# EMMC_CHIP.net
KiCad netlist of a schematic drawn in Altium Designer
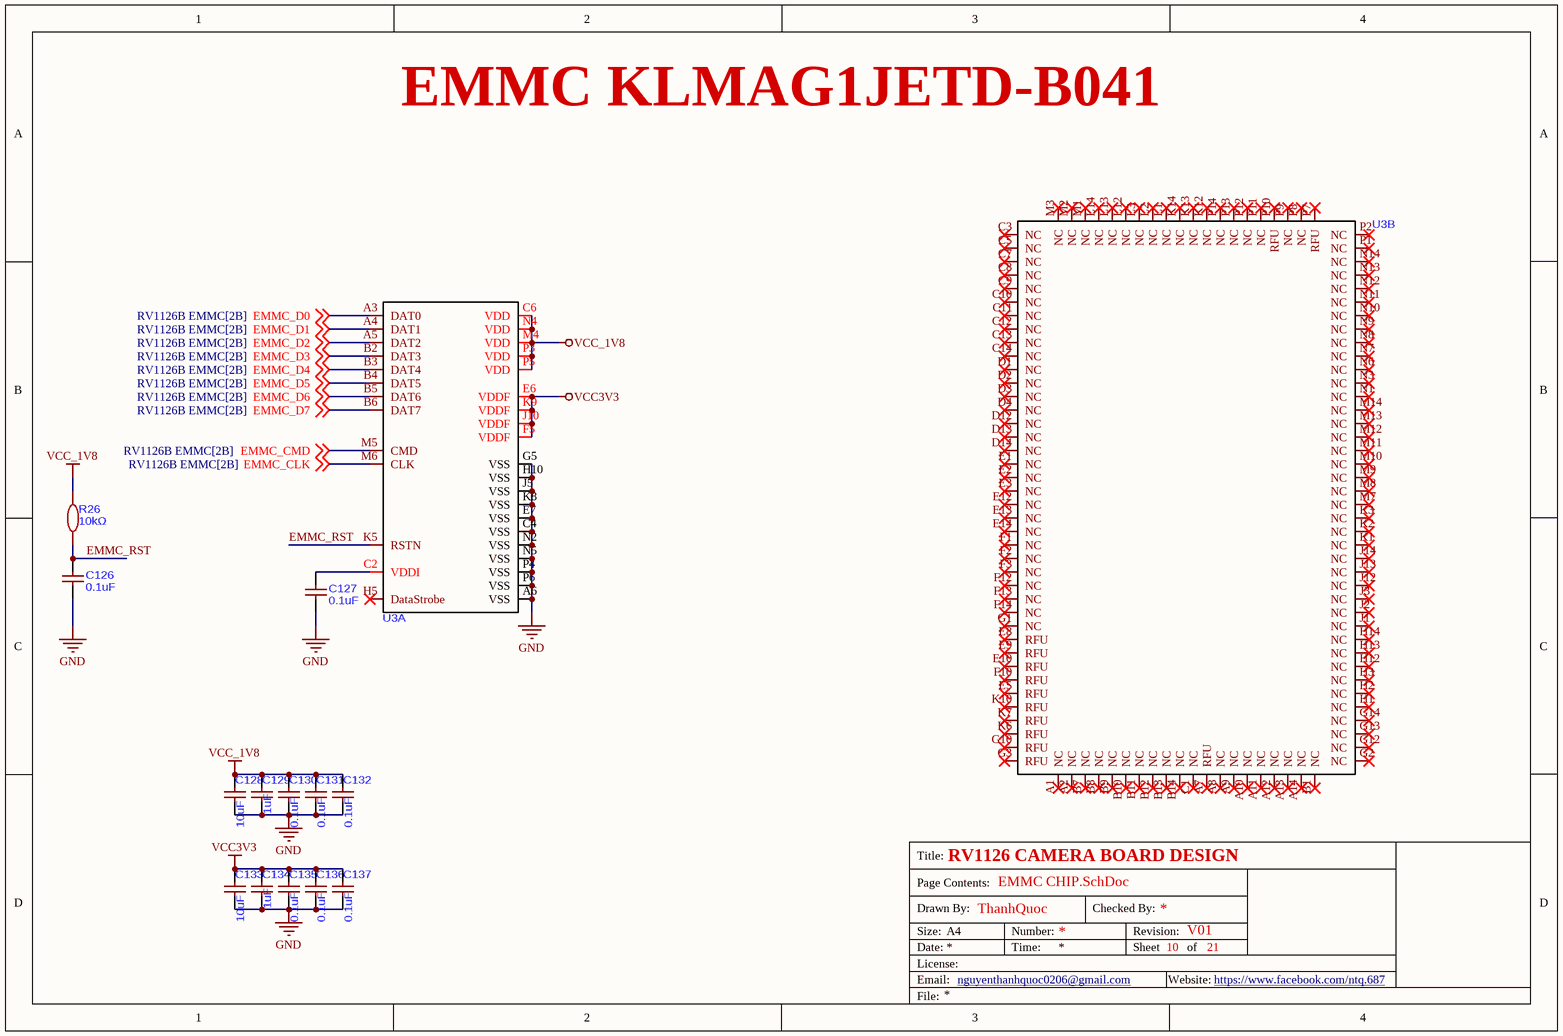
[diagram p0: EMMC CHIP.SchDoc]

(export (version "E")
  (design (tool "Eeschema 10.0.6"))
  (components
    (comp (ref "C126")
      (value "0.1uF")
      (footprint "C0201")
      (description "0.1uF ±10% 6.3V Ceramic Capacitor X5R 0201")
      (libsource (lib "Schlib1") (part "CAP_100nF-6.3V-10%-0201_1"))
    )
    (comp (ref "C127")
      (value "0.1uF")
      (footprint "C0201")
      (description "0.1uF ±10% 6.3V Ceramic Capacitor X5R 0201")
      (libsource (lib "Schlib1") (part "CAP_100nF-6.3V-10%-0201_1"))
    )
    (comp (ref "C128")
      (value "10uF")
      (footprint "C0402")
      (description "10µF ±20% 10V Ceramic Capacitor X5R 0402 (1005 Metric)")
      (libsource (lib "Schlib1") (part "CAP_10uF-10V-20%-0402"))
    )
    (comp (ref "C129")
      (value "1uF")
      (footprint "C0201")
      (description "1uF ±10% 6.3V Ceramic Capacitor X5R 0201")
      (libsource (lib "Schlib1") (part "CAP_1uF-6.3V-10%-0201"))
    )
    (comp (ref "C130")
      (value "0.1uF")
      (footprint "C0201")
      (description "0.1uF ±10% 6.3V Ceramic Capacitor X5R 0201")
      (libsource (lib "Schlib1") (part "CAP_100nF-6.3V-10%-0201_1"))
    )
    (comp (ref "C131")
      (value "0.1uF")
      (footprint "C0201")
      (description "0.1uF ±10% 6.3V Ceramic Capacitor X5R 0201")
      (libsource (lib "Schlib1") (part "CAP_100nF-6.3V-10%-0201_1"))
    )
    (comp (ref "C132")
      (value "0.1uF")
      (footprint "C0201")
      (description "0.1uF ±10% 6.3V Ceramic Capacitor X5R 0201")
      (libsource (lib "Schlib1") (part "CAP_100nF-6.3V-10%-0201_1"))
    )
    (comp (ref "C133")
      (value "10uF")
      (footprint "C0402")
      (description "10µF ±20% 10V Ceramic Capacitor X5R 0402 (1005 Metric)")
      (libsource (lib "Schlib1") (part "CAP_10uF-10V-20%-0402"))
    )
    (comp (ref "C134")
      (value "1uF")
      (footprint "C0201")
      (description "1uF ±10% 6.3V Ceramic Capacitor X5R 0201")
      (libsource (lib "Schlib1") (part "CAP_1uF-6.3V-10%-0201"))
    )
    (comp (ref "C135")
      (value "0.1uF")
      (footprint "C0201")
      (description "0.1uF ±10% 6.3V Ceramic Capacitor X5R 0201")
      (libsource (lib "Schlib1") (part "CAP_100nF-6.3V-10%-0201_1"))
    )
    (comp (ref "C136")
      (value "0.1uF")
      (footprint "C0201")
      (description "0.1uF ±10% 6.3V Ceramic Capacitor X5R 0201")
      (libsource (lib "Schlib1") (part "CAP_100nF-6.3V-10%-0201_1"))
    )
    (comp (ref "C137")
      (value "0.1uF")
      (footprint "C0201")
      (description "0.1uF ±10% 6.3V Ceramic Capacitor X5R 0201")
      (libsource (lib "Schlib1") (part "CAP_100nF-6.3V-10%-0201_1"))
    )
    (comp (ref "R26")
      (value "10kΩ")
      (footprint "R0201")
      (description "RES 10KΩ ±1% 50mW 0201")
      (libsource (lib "Schlib1") (part "RES_10K-50mW-1%-0201"))
    )
    (comp (ref "U3")
      (value "emmc 16gb")
      (footprint "FBGA-153_L13.0-W11.5-P0.50_KLMAG1JETD-B041")
      (description "eMMC 5.1 Specification compatibility")
      (libsource (lib "Schlib1") (part "KLMAG1JETD-B041"))
    )
  )
  (nets
    (net (code "1") (name "/EMMC_RST") (class "Default")
      (node (ref "C126") (pin "2") (pinfunction "2_2") (pintype "passive"))
      (node (ref "R26") (pin "1") (pinfunction "1_1") (pintype "passive"))
      (node (ref "U3") (pin "K5") (pinfunction "RSTN_K5") (pintype "passive"))
    )
    (net (code "2") (name "EMMC_CLK") (class "Default")
      (node (ref "U3") (pin "M6") (pinfunction "CLK_M6") (pintype "passive"))
    )
    (net (code "3") (name "EMMC_CMD") (class "Default")
      (node (ref "U3") (pin "M5") (pinfunction "CMD_M5") (pintype "passive"))
    )
    (net (code "4") (name "EMMC_D0") (class "Default")
      (node (ref "U3") (pin "A3") (pinfunction "DAT0_A3") (pintype "passive"))
    )
    (net (code "5") (name "EMMC_D1") (class "Default")
      (node (ref "U3") (pin "A4") (pinfunction "DAT1_A4") (pintype "passive"))
    )
    (net (code "6") (name "EMMC_D2") (class "Default")
      (node (ref "U3") (pin "A5") (pinfunction "DAT2_A5") (pintype "passive"))
    )
    (net (code "7") (name "EMMC_D3") (class "Default")
      (node (ref "U3") (pin "B2") (pinfunction "DAT3_B2") (pintype "passive"))
    )
    (net (code "8") (name "EMMC_D4") (class "Default")
      (node (ref "U3") (pin "B3") (pinfunction "DAT4_B3") (pintype "passive"))
    )
    (net (code "9") (name "EMMC_D5") (class "Default")
      (node (ref "U3") (pin "B4") (pinfunction "DAT5_B4") (pintype "passive"))
    )
    (net (code "10") (name "EMMC_D6") (class "Default")
      (node (ref "U3") (pin "B5") (pinfunction "DAT6_B5") (pintype "passive"))
    )
    (net (code "11") (name "EMMC_D7") (class "Default")
      (node (ref "U3") (pin "B6") (pinfunction "DAT7_B6") (pintype "passive"))
    )
    (net (code "12") (name "GND") (class "Default")
      (node (ref "C126") (pin "1") (pinfunction "1_1") (pintype "passive"))
      (node (ref "C127") (pin "1") (pinfunction "1_1") (pintype "passive"))
      (node (ref "C128") (pin "1") (pinfunction "1_1") (pintype "passive"))
      (node (ref "C129") (pin "1") (pinfunction "1_1") (pintype "passive"))
      (node (ref "C130") (pin "1") (pinfunction "1_1") (pintype "passive"))
      (node (ref "C131") (pin "1") (pinfunction "1_1") (pintype "passive"))
      (node (ref "C132") (pin "1") (pinfunction "1_1") (pintype "passive"))
      (node (ref "C133") (pin "1") (pinfunction "1_1") (pintype "passive"))
      (node (ref "C134") (pin "1") (pinfunction "1_1") (pintype "passive"))
      (node (ref "C135") (pin "1") (pinfunction "1_1") (pintype "passive"))
      (node (ref "C136") (pin "1") (pinfunction "1_1") (pintype "passive"))
      (node (ref "C137") (pin "1") (pinfunction "1_1") (pintype "passive"))
      (node (ref "U3") (pin "A6") (pinfunction "VSS_A6") (pintype "passive"))
      (node (ref "U3") (pin "C4") (pinfunction "VSS_C4") (pintype "passive"))
      (node (ref "U3") (pin "E7") (pinfunction "VSS_E7") (pintype "passive"))
      (node (ref "U3") (pin "G5") (pinfunction "VSS_G5") (pintype "passive"))
      (node (ref "U3") (pin "H10") (pinfunction "VSS_H10") (pintype "passive"))
      (node (ref "U3") (pin "J5") (pinfunction "VSS_J5") (pintype "passive"))
      (node (ref "U3") (pin "K8") (pinfunction "VSS_K8") (pintype "passive"))
      (node (ref "U3") (pin "N2") (pinfunction "VSS_N2") (pintype "passive"))
      (node (ref "U3") (pin "N5") (pinfunction "VSS_N5") (pintype "passive"))
      (node (ref "U3") (pin "P4") (pinfunction "VSS_P4") (pintype "passive"))
      (node (ref "U3") (pin "P6") (pinfunction "VSS_P6") (pintype "passive"))
    )
    (net (code "13") (name "Net-(U3A-VDDI)") (class "Default")
      (node (ref "C127") (pin "2") (pinfunction "2_2") (pintype "passive"))
      (node (ref "U3") (pin "C2") (pinfunction "VDDI_C2") (pintype "passive"))
    )
    (net (code "14") (name "VCC3V3") (class "Default")
      (node (ref "C133") (pin "2") (pinfunction "2_2") (pintype "passive"))
      (node (ref "C134") (pin "2") (pinfunction "2_2") (pintype "passive"))
      (node (ref "C135") (pin "2") (pinfunction "2_2") (pintype "passive"))
      (node (ref "C136") (pin "2") (pinfunction "2_2") (pintype "passive"))
      (node (ref "C137") (pin "2") (pinfunction "2_2") (pintype "passive"))
      (node (ref "U3") (pin "E6") (pinfunction "VDDF_E6") (pintype "passive"))
      (node (ref "U3") (pin "F5") (pinfunction "VDDF_F5") (pintype "passive"))
      (node (ref "U3") (pin "J10") (pinfunction "VDDF_J10") (pintype "passive"))
      (node (ref "U3") (pin "K9") (pinfunction "VDDF_K9") (pintype "passive"))
    )
    (net (code "15") (name "VCC_1V8") (class "Default")
      (node (ref "C128") (pin "2") (pinfunction "2_2") (pintype "passive"))
      (node (ref "C129") (pin "2") (pinfunction "2_2") (pintype "passive"))
      (node (ref "C130") (pin "2") (pinfunction "2_2") (pintype "passive"))
      (node (ref "C131") (pin "2") (pinfunction "2_2") (pintype "passive"))
      (node (ref "C132") (pin "2") (pinfunction "2_2") (pintype "passive"))
      (node (ref "R26") (pin "2") (pinfunction "2_2") (pintype "passive"))
      (node (ref "U3") (pin "C6") (pinfunction "VDD_C6") (pintype "passive"))
      (node (ref "U3") (pin "M4") (pinfunction "VDD_M4") (pintype "passive"))
      (node (ref "U3") (pin "N4") (pinfunction "VDD_N4") (pintype "passive"))
      (node (ref "U3") (pin "P3") (pinfunction "VDD_P3") (pintype "passive"))
      (node (ref "U3") (pin "P5") (pinfunction "VDD_P5") (pintype "passive"))
    )
    (net (code "16") (name "unconnected-(U3A-DataStrobe-PadH5)") (class "Default")
      (node (ref "U3") (pin "H5") (pinfunction "DataStrobe_H5") (pintype "passive+no_connect"))
    )
    (net (code "17") (name "unconnected-(U3B-NC-PadA1)") (class "Default")
      (node (ref "U3") (pin "A1") (pinfunction "NC_A1") (pintype "passive+no_connect"))
    )
    (net (code "18") (name "unconnected-(U3B-NC-PadA2)") (class "Default")
      (node (ref "U3") (pin "A2") (pinfunction "NC_A2") (pintype "passive+no_connect"))
    )
    (net (code "19") (name "unconnected-(U3B-NC-PadA8)") (class "Default")
      (node (ref "U3") (pin "A8") (pinfunction "NC_A8") (pintype "passive+no_connect"))
    )
    (net (code "20") (name "unconnected-(U3B-NC-PadA9)") (class "Default")
      (node (ref "U3") (pin "A9") (pinfunction "NC_A9") (pintype "passive+no_connect"))
    )
    (net (code "21") (name "unconnected-(U3B-NC-PadA10)") (class "Default")
      (node (ref "U3") (pin "A10") (pinfunction "NC_A10") (pintype "passive+no_connect"))
    )
    (net (code "22") (name "unconnected-(U3B-NC-PadA11)") (class "Default")
      (node (ref "U3") (pin "A11") (pinfunction "NC_A11") (pintype "passive+no_connect"))
    )
    (net (code "23") (name "unconnected-(U3B-NC-PadA12)") (class "Default")
      (node (ref "U3") (pin "A12") (pinfunction "NC_A12") (pintype "passive+no_connect"))
    )
    (net (code "24") (name "unconnected-(U3B-NC-PadA13)") (class "Default")
      (node (ref "U3") (pin "A13") (pinfunction "NC_A13") (pintype "passive+no_connect"))
    )
    (net (code "25") (name "unconnected-(U3B-NC-PadA14)") (class "Default")
      (node (ref "U3") (pin "A14") (pinfunction "NC_A14") (pintype "passive+no_connect"))
    )
    (net (code "26") (name "unconnected-(U3B-NC-PadB1)") (class "Default")
      (node (ref "U3") (pin "B1") (pinfunction "NC_B1") (pintype "passive+no_connect"))
    )
    (net (code "27") (name "unconnected-(U3B-NC-PadB7)") (class "Default")
      (node (ref "U3") (pin "B7") (pinfunction "NC_B7") (pintype "passive+no_connect"))
    )
    (net (code "28") (name "unconnected-(U3B-NC-PadB8)") (class "Default")
      (node (ref "U3") (pin "B8") (pinfunction "NC_B8") (pintype "passive+no_connect"))
    )
    (net (code "29") (name "unconnected-(U3B-NC-PadB9)") (class "Default")
      (node (ref "U3") (pin "B9") (pinfunction "NC_B9") (pintype "passive+no_connect"))
    )
    (net (code "30") (name "unconnected-(U3B-NC-PadB10)") (class "Default")
      (node (ref "U3") (pin "B10") (pinfunction "NC_B10") (pintype "passive+no_connect"))
    )
    (net (code "31") (name "unconnected-(U3B-NC-PadB11)") (class "Default")
      (node (ref "U3") (pin "B11") (pinfunction "NC_B11") (pintype "passive+no_connect"))
    )
    (net (code "32") (name "unconnected-(U3B-NC-PadB12)") (class "Default")
      (node (ref "U3") (pin "B12") (pinfunction "NC_B12") (pintype "passive+no_connect"))
    )
    (net (code "33") (name "unconnected-(U3B-NC-PadB13)") (class "Default")
      (node (ref "U3") (pin "B13") (pinfunction "NC_B13") (pintype "passive+no_connect"))
    )
    (net (code "34") (name "unconnected-(U3B-NC-PadB14)") (class "Default")
      (node (ref "U3") (pin "B14") (pinfunction "NC_B14") (pintype "passive+no_connect"))
    )
    (net (code "35") (name "unconnected-(U3B-NC-PadC1)") (class "Default")
      (node (ref "U3") (pin "C1") (pinfunction "NC_C1") (pintype "passive+no_connect"))
    )
    (net (code "36") (name "unconnected-(U3B-NC-PadC3)") (class "Default")
      (node (ref "U3") (pin "C3") (pinfunction "NC_C3") (pintype "passive+no_connect"))
    )
    (net (code "37") (name "unconnected-(U3B-NC-PadC5)") (class "Default")
      (node (ref "U3") (pin "C5") (pinfunction "NC_C5") (pintype "passive+no_connect"))
    )
    (net (code "38") (name "unconnected-(U3B-NC-PadC7)") (class "Default")
      (node (ref "U3") (pin "C7") (pinfunction "NC_C7") (pintype "passive+no_connect"))
    )
    (net (code "39") (name "unconnected-(U3B-NC-PadC8)") (class "Default")
      (node (ref "U3") (pin "C8") (pinfunction "NC_C8") (pintype "passive+no_connect"))
    )
    (net (code "40") (name "unconnected-(U3B-NC-PadC9)") (class "Default")
      (node (ref "U3") (pin "C9") (pinfunction "NC_C9") (pintype "passive+no_connect"))
    )
    (net (code "41") (name "unconnected-(U3B-NC-PadC10)") (class "Default")
      (node (ref "U3") (pin "C10") (pinfunction "NC_C10") (pintype "passive+no_connect"))
    )
    (net (code "42") (name "unconnected-(U3B-NC-PadC11)") (class "Default")
      (node (ref "U3") (pin "C11") (pinfunction "NC_C11") (pintype "passive+no_connect"))
    )
    (net (code "43") (name "unconnected-(U3B-NC-PadC12)") (class "Default")
      (node (ref "U3") (pin "C12") (pinfunction "NC_C12") (pintype "passive+no_connect"))
    )
    (net (code "44") (name "unconnected-(U3B-NC-PadC13)") (class "Default")
      (node (ref "U3") (pin "C13") (pinfunction "NC_C13") (pintype "passive+no_connect"))
    )
    (net (code "45") (name "unconnected-(U3B-NC-PadC14)") (class "Default")
      (node (ref "U3") (pin "C14") (pinfunction "NC_C14") (pintype "passive+no_connect"))
    )
    (net (code "46") (name "unconnected-(U3B-NC-PadD1)") (class "Default")
      (node (ref "U3") (pin "D1") (pinfunction "NC_D1") (pintype "passive+no_connect"))
    )
    (net (code "47") (name "unconnected-(U3B-NC-PadD2)") (class "Default")
      (node (ref "U3") (pin "D2") (pinfunction "NC_D2") (pintype "passive+no_connect"))
    )
    (net (code "48") (name "unconnected-(U3B-NC-PadD3)") (class "Default")
      (node (ref "U3") (pin "D3") (pinfunction "NC_D3") (pintype "passive+no_connect"))
    )
    (net (code "49") (name "unconnected-(U3B-NC-PadD4)") (class "Default")
      (node (ref "U3") (pin "D4") (pinfunction "NC_D4") (pintype "passive+no_connect"))
    )
    (net (code "50") (name "unconnected-(U3B-NC-PadD12)") (class "Default")
      (node (ref "U3") (pin "D12") (pinfunction "NC_D12") (pintype "passive+no_connect"))
    )
    (net (code "51") (name "unconnected-(U3B-NC-PadD13)") (class "Default")
      (node (ref "U3") (pin "D13") (pinfunction "NC_D13") (pintype "passive+no_connect"))
    )
    (net (code "52") (name "unconnected-(U3B-NC-PadD14)") (class "Default")
      (node (ref "U3") (pin "D14") (pinfunction "NC_D14") (pintype "passive+no_connect"))
    )
    (net (code "53") (name "unconnected-(U3B-NC-PadE1)") (class "Default")
      (node (ref "U3") (pin "E1") (pinfunction "NC_E1") (pintype "passive+no_connect"))
    )
    (net (code "54") (name "unconnected-(U3B-NC-PadE2)") (class "Default")
      (node (ref "U3") (pin "E2") (pinfunction "NC_E2") (pintype "passive+no_connect"))
    )
    (net (code "55") (name "unconnected-(U3B-NC-PadE3)") (class "Default")
      (node (ref "U3") (pin "E3") (pinfunction "NC_E3") (pintype "passive+no_connect"))
    )
    (net (code "56") (name "unconnected-(U3B-NC-PadE12)") (class "Default")
      (node (ref "U3") (pin "E12") (pinfunction "NC_E12") (pintype "passive+no_connect"))
    )
    (net (code "57") (name "unconnected-(U3B-NC-PadE13)") (class "Default")
      (node (ref "U3") (pin "E13") (pinfunction "NC_E13") (pintype "passive+no_connect"))
    )
    (net (code "58") (name "unconnected-(U3B-NC-PadE14)") (class "Default")
      (node (ref "U3") (pin "E14") (pinfunction "NC_E14") (pintype "passive+no_connect"))
    )
    (net (code "59") (name "unconnected-(U3B-NC-PadF1)") (class "Default")
      (node (ref "U3") (pin "F1") (pinfunction "NC_F1") (pintype "passive+no_connect"))
    )
    (net (code "60") (name "unconnected-(U3B-NC-PadF2)") (class "Default")
      (node (ref "U3") (pin "F2") (pinfunction "NC_F2") (pintype "passive+no_connect"))
    )
    (net (code "61") (name "unconnected-(U3B-NC-PadF3)") (class "Default")
      (node (ref "U3") (pin "F3") (pinfunction "NC_F3") (pintype "passive+no_connect"))
    )
    (net (code "62") (name "unconnected-(U3B-NC-PadF12)") (class "Default")
      (node (ref "U3") (pin "F12") (pinfunction "NC_F12") (pintype "passive+no_connect"))
    )
    (net (code "63") (name "unconnected-(U3B-NC-PadF13)") (class "Default")
      (node (ref "U3") (pin "F13") (pinfunction "NC_F13") (pintype "passive+no_connect"))
    )
    (net (code "64") (name "unconnected-(U3B-NC-PadF14)") (class "Default")
      (node (ref "U3") (pin "F14") (pinfunction "NC_F14") (pintype "passive+no_connect"))
    )
    (net (code "65") (name "unconnected-(U3B-NC-PadG1)") (class "Default")
      (node (ref "U3") (pin "G1") (pinfunction "NC_G1") (pintype "passive+no_connect"))
    )
    (net (code "66") (name "unconnected-(U3B-NC-PadG2)") (class "Default")
      (node (ref "U3") (pin "G2") (pinfunction "NC_G2") (pintype "passive+no_connect"))
    )
    (net (code "67") (name "unconnected-(U3B-NC-PadG12)") (class "Default")
      (node (ref "U3") (pin "G12") (pinfunction "NC_G12") (pintype "passive+no_connect"))
    )
    (net (code "68") (name "unconnected-(U3B-NC-PadG13)") (class "Default")
      (node (ref "U3") (pin "G13") (pinfunction "NC_G13") (pintype "passive+no_connect"))
    )
    (net (code "69") (name "unconnected-(U3B-NC-PadG14)") (class "Default")
      (node (ref "U3") (pin "G14") (pinfunction "NC_G14") (pintype "passive+no_connect"))
    )
    (net (code "70") (name "unconnected-(U3B-NC-PadH1)") (class "Default")
      (node (ref "U3") (pin "H1") (pinfunction "NC_H1") (pintype "passive+no_connect"))
    )
    (net (code "71") (name "unconnected-(U3B-NC-PadH2)") (class "Default")
      (node (ref "U3") (pin "H2") (pinfunction "NC_H2") (pintype "passive+no_connect"))
    )
    (net (code "72") (name "unconnected-(U3B-NC-PadH3)") (class "Default")
      (node (ref "U3") (pin "H3") (pinfunction "NC_H3") (pintype "passive+no_connect"))
    )
    (net (code "73") (name "unconnected-(U3B-NC-PadH12)") (class "Default")
      (node (ref "U3") (pin "H12") (pinfunction "NC_H12") (pintype "passive+no_connect"))
    )
    (net (code "74") (name "unconnected-(U3B-NC-PadH13)") (class "Default")
      (node (ref "U3") (pin "H13") (pinfunction "NC_H13") (pintype "passive+no_connect"))
    )
    (net (code "75") (name "unconnected-(U3B-NC-PadH14)") (class "Default")
      (node (ref "U3") (pin "H14") (pinfunction "NC_H14") (pintype "passive+no_connect"))
    )
    (net (code "76") (name "unconnected-(U3B-NC-PadJ1)") (class "Default")
      (node (ref "U3") (pin "J1") (pinfunction "NC_J1") (pintype "passive+no_connect"))
    )
    (net (code "77") (name "unconnected-(U3B-NC-PadJ2)") (class "Default")
      (node (ref "U3") (pin "J2") (pinfunction "NC_J2") (pintype "passive+no_connect"))
    )
    (net (code "78") (name "unconnected-(U3B-NC-PadJ3)") (class "Default")
      (node (ref "U3") (pin "J3") (pinfunction "NC_J3") (pintype "passive+no_connect"))
    )
    (net (code "79") (name "unconnected-(U3B-NC-PadJ12)") (class "Default")
      (node (ref "U3") (pin "J12") (pinfunction "NC_J12") (pintype "passive+no_connect"))
    )
    (net (code "80") (name "unconnected-(U3B-NC-PadJ13)") (class "Default")
      (node (ref "U3") (pin "J13") (pinfunction "NC_J13") (pintype "passive+no_connect"))
    )
    (net (code "81") (name "unconnected-(U3B-NC-PadJ14)") (class "Default")
      (node (ref "U3") (pin "J14") (pinfunction "NC_J14") (pintype "passive+no_connect"))
    )
    (net (code "82") (name "unconnected-(U3B-NC-PadK1)") (class "Default")
      (node (ref "U3") (pin "K1") (pinfunction "NC_K1") (pintype "passive+no_connect"))
    )
    (net (code "83") (name "unconnected-(U3B-NC-PadK2)") (class "Default")
      (node (ref "U3") (pin "K2") (pinfunction "NC_K2") (pintype "passive+no_connect"))
    )
    (net (code "84") (name "unconnected-(U3B-NC-PadK3)") (class "Default")
      (node (ref "U3") (pin "K3") (pinfunction "NC_K3") (pintype "passive+no_connect"))
    )
    (net (code "85") (name "unconnected-(U3B-NC-PadK12)") (class "Default")
      (node (ref "U3") (pin "K12") (pinfunction "NC_K12") (pintype "passive+no_connect"))
    )
    (net (code "86") (name "unconnected-(U3B-NC-PadK13)") (class "Default")
      (node (ref "U3") (pin "K13") (pinfunction "NC_K13") (pintype "passive+no_connect"))
    )
    (net (code "87") (name "unconnected-(U3B-NC-PadK14)") (class "Default")
      (node (ref "U3") (pin "K14") (pinfunction "NC_K14") (pintype "passive+no_connect"))
    )
    (net (code "88") (name "unconnected-(U3B-NC-PadL1)") (class "Default")
      (node (ref "U3") (pin "L1") (pinfunction "NC_L1") (pintype "passive+no_connect"))
    )
    (net (code "89") (name "unconnected-(U3B-NC-PadL2)") (class "Default")
      (node (ref "U3") (pin "L2") (pinfunction "NC_L2") (pintype "passive+no_connect"))
    )
    (net (code "90") (name "unconnected-(U3B-NC-PadL3)") (class "Default")
      (node (ref "U3") (pin "L3") (pinfunction "NC_L3") (pintype "passive+no_connect"))
    )
    (net (code "91") (name "unconnected-(U3B-NC-PadL12)") (class "Default")
      (node (ref "U3") (pin "L12") (pinfunction "NC_L12") (pintype "passive+no_connect"))
    )
    (net (code "92") (name "unconnected-(U3B-NC-PadL13)") (class "Default")
      (node (ref "U3") (pin "L13") (pinfunction "NC_L13") (pintype "passive+no_connect"))
    )
    (net (code "93") (name "unconnected-(U3B-NC-PadL14)") (class "Default")
      (node (ref "U3") (pin "L14") (pinfunction "NC_L14") (pintype "passive+no_connect"))
    )
    (net (code "94") (name "unconnected-(U3B-NC-PadM1)") (class "Default")
      (node (ref "U3") (pin "M1") (pinfunction "NC_M1") (pintype "passive+no_connect"))
    )
    (net (code "95") (name "unconnected-(U3B-NC-PadM2)") (class "Default")
      (node (ref "U3") (pin "M2") (pinfunction "NC_M2") (pintype "passive+no_connect"))
    )
    (net (code "96") (name "unconnected-(U3B-NC-PadM3)") (class "Default")
      (node (ref "U3") (pin "M3") (pinfunction "NC_M3") (pintype "passive+no_connect"))
    )
    (net (code "97") (name "unconnected-(U3B-NC-PadM7)") (class "Default")
      (node (ref "U3") (pin "M7") (pinfunction "NC_M7") (pintype "passive+no_connect"))
    )
    (net (code "98") (name "unconnected-(U3B-NC-PadM8)") (class "Default")
      (node (ref "U3") (pin "M8") (pinfunction "NC_M8") (pintype "passive+no_connect"))
    )
    (net (code "99") (name "unconnected-(U3B-NC-PadM9)") (class "Default")
      (node (ref "U3") (pin "M9") (pinfunction "NC_M9") (pintype "passive+no_connect"))
    )
    (net (code "100") (name "unconnected-(U3B-NC-PadM10)") (class "Default")
      (node (ref "U3") (pin "M10") (pinfunction "NC_M10") (pintype "passive+no_connect"))
    )
    (net (code "101") (name "unconnected-(U3B-NC-PadM11)") (class "Default")
      (node (ref "U3") (pin "M11") (pinfunction "NC_M11") (pintype "passive+no_connect"))
    )
    (net (code "102") (name "unconnected-(U3B-NC-PadM12)") (class "Default")
      (node (ref "U3") (pin "M12") (pinfunction "NC_M12") (pintype "passive+no_connect"))
    )
    (net (code "103") (name "unconnected-(U3B-NC-PadM13)") (class "Default")
      (node (ref "U3") (pin "M13") (pinfunction "NC_M13") (pintype "passive+no_connect"))
    )
    (net (code "104") (name "unconnected-(U3B-NC-PadM14)") (class "Default")
      (node (ref "U3") (pin "M14") (pinfunction "NC_M14") (pintype "passive+no_connect"))
    )
    (net (code "105") (name "unconnected-(U3B-NC-PadN1)") (class "Default")
      (node (ref "U3") (pin "N1") (pinfunction "NC_N1") (pintype "passive+no_connect"))
    )
    (net (code "106") (name "unconnected-(U3B-NC-PadN3)") (class "Default")
      (node (ref "U3") (pin "N3") (pinfunction "NC_N3") (pintype "passive+no_connect"))
    )
    (net (code "107") (name "unconnected-(U3B-NC-PadN6)") (class "Default")
      (node (ref "U3") (pin "N6") (pinfunction "NC_N6") (pintype "passive+no_connect"))
    )
    (net (code "108") (name "unconnected-(U3B-NC-PadN7)") (class "Default")
      (node (ref "U3") (pin "N7") (pinfunction "NC_N7") (pintype "passive+no_connect"))
    )
    (net (code "109") (name "unconnected-(U3B-NC-PadN8)") (class "Default")
      (node (ref "U3") (pin "N8") (pinfunction "NC_N8") (pintype "passive+no_connect"))
    )
    (net (code "110") (name "unconnected-(U3B-NC-PadN9)") (class "Default")
      (node (ref "U3") (pin "N9") (pinfunction "NC_N9") (pintype "passive+no_connect"))
    )
    (net (code "111") (name "unconnected-(U3B-NC-PadN10)") (class "Default")
      (node (ref "U3") (pin "N10") (pinfunction "NC_N10") (pintype "passive+no_connect"))
    )
    (net (code "112") (name "unconnected-(U3B-NC-PadN11)") (class "Default")
      (node (ref "U3") (pin "N11") (pinfunction "NC_N11") (pintype "passive+no_connect"))
    )
    (net (code "113") (name "unconnected-(U3B-NC-PadN12)") (class "Default")
      (node (ref "U3") (pin "N12") (pinfunction "NC_N12") (pintype "passive+no_connect"))
    )
    (net (code "114") (name "unconnected-(U3B-NC-PadN13)") (class "Default")
      (node (ref "U3") (pin "N13") (pinfunction "NC_N13") (pintype "passive+no_connect"))
    )
    (net (code "115") (name "unconnected-(U3B-NC-PadN14)") (class "Default")
      (node (ref "U3") (pin "N14") (pinfunction "NC_N14") (pintype "passive+no_connect"))
    )
    (net (code "116") (name "unconnected-(U3B-NC-PadP1)") (class "Default")
      (node (ref "U3") (pin "P1") (pinfunction "NC_P1") (pintype "passive+no_connect"))
    )
    (net (code "117") (name "unconnected-(U3B-NC-PadP2)") (class "Default")
      (node (ref "U3") (pin "P2") (pinfunction "NC_P2") (pintype "passive+no_connect"))
    )
    (net (code "118") (name "unconnected-(U3B-NC-PadP8)") (class "Default")
      (node (ref "U3") (pin "P8") (pinfunction "NC_P8") (pintype "passive+no_connect"))
    )
    (net (code "119") (name "unconnected-(U3B-NC-PadP9)") (class "Default")
      (node (ref "U3") (pin "P9") (pinfunction "NC_P9") (pintype "passive+no_connect"))
    )
    (net (code "120") (name "unconnected-(U3B-NC-PadP11)") (class "Default")
      (node (ref "U3") (pin "P11") (pinfunction "NC_P11") (pintype "passive+no_connect"))
    )
    (net (code "121") (name "unconnected-(U3B-NC-PadP12)") (class "Default")
      (node (ref "U3") (pin "P12") (pinfunction "NC_P12") (pintype "passive+no_connect"))
    )
    (net (code "122") (name "unconnected-(U3B-NC-PadP13)") (class "Default")
      (node (ref "U3") (pin "P13") (pinfunction "NC_P13") (pintype "passive+no_connect"))
    )
    (net (code "123") (name "unconnected-(U3B-NC-PadP14)") (class "Default")
      (node (ref "U3") (pin "P14") (pinfunction "NC_P14") (pintype "passive+no_connect"))
    )
    (net (code "124") (name "unconnected-(U3B-RFU-PadA7)") (class "Default")
      (node (ref "U3") (pin "A7") (pinfunction "RFU_A7") (pintype "passive+no_connect"))
    )
    (net (code "125") (name "unconnected-(U3B-RFU-PadE5)") (class "Default")
      (node (ref "U3") (pin "E5") (pinfunction "RFU_E5") (pintype "passive+no_connect"))
    )
    (net (code "126") (name "unconnected-(U3B-RFU-PadE8)") (class "Default")
      (node (ref "U3") (pin "E8") (pinfunction "RFU_E8") (pintype "passive+no_connect"))
    )
    (net (code "127") (name "unconnected-(U3B-RFU-PadE9)") (class "Default")
      (node (ref "U3") (pin "E9") (pinfunction "RFU_E9") (pintype "passive+no_connect"))
    )
    (net (code "128") (name "unconnected-(U3B-RFU-PadE10)") (class "Default")
      (node (ref "U3") (pin "E10") (pinfunction "RFU_E10") (pintype "passive+no_connect"))
    )
    (net (code "129") (name "unconnected-(U3B-RFU-PadF10)") (class "Default")
      (node (ref "U3") (pin "F10") (pinfunction "RFU_F10") (pintype "passive+no_connect"))
    )
    (net (code "130") (name "unconnected-(U3B-RFU-PadG3)") (class "Default")
      (node (ref "U3") (pin "G3") (pinfunction "RFU_G3") (pintype "passive+no_connect"))
    )
    (net (code "131") (name "unconnected-(U3B-RFU-PadG10)") (class "Default")
      (node (ref "U3") (pin "G10") (pinfunction "RFU_G10") (pintype "passive+no_connect"))
    )
    (net (code "132") (name "unconnected-(U3B-RFU-PadK6)") (class "Default")
      (node (ref "U3") (pin "K6") (pinfunction "RFU_K6") (pintype "passive+no_connect"))
    )
    (net (code "133") (name "unconnected-(U3B-RFU-PadK7)") (class "Default")
      (node (ref "U3") (pin "K7") (pinfunction "RFU_K7") (pintype "passive+no_connect"))
    )
    (net (code "134") (name "unconnected-(U3B-RFU-PadK10)") (class "Default")
      (node (ref "U3") (pin "K10") (pinfunction "RFU_K10") (pintype "passive+no_connect"))
    )
    (net (code "135") (name "unconnected-(U3B-RFU-PadP7)") (class "Default")
      (node (ref "U3") (pin "P7") (pinfunction "RFU_P7") (pintype "passive+no_connect"))
    )
    (net (code "136") (name "unconnected-(U3B-RFU-PadP10)") (class "Default")
      (node (ref "U3") (pin "P10") (pinfunction "RFU_P10") (pintype "passive+no_connect"))
    )
  )
)
